# H_bridge.net
KiCad netlist of a schematic drawn in EAGLE
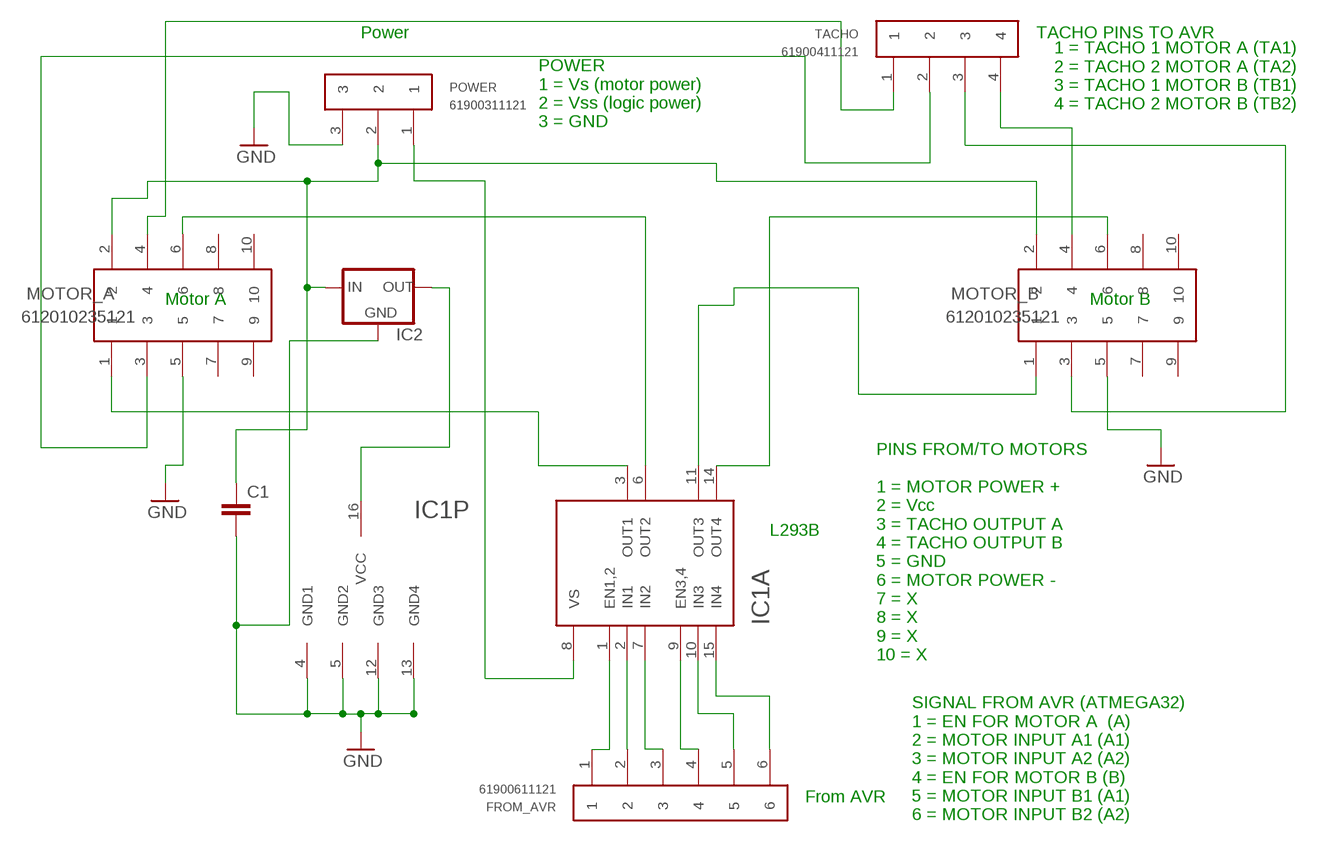
[diagram p0: schematic, sheet 1]

(export (version "E")
  (design (tool "Eeschema 10.0.6"))
  (components
    (comp (ref "C1")
      (value "C7.5/5")
      (footprint "eagle-import:C7.5B5")
      (libsource (lib "eagle-import") (part "C7.5/5"))
    )
    (comp (ref "FROM_AVR")
      (value "61900611121")
      (footprint "eagle-import:61900611121")
      (libsource (lib "eagle-import") (part "61900611121"))
    )
    (comp (ref "IC1")
      (value "L293D")
      (footprint "eagle-import:DIP16")
      (libsource (lib "eagle-import") (part "L293D"))
    )
    (comp (ref "IC2")
      (value "V_REG_78XX-TO-220")
      (footprint "eagle-import:TO-220-ALT")
      (libsource (lib "eagle-import") (part "V_REG_78XX-TO-220"))
    )
    (comp (ref "MOTOR_A")
      (value "612010235121")
      (footprint "eagle-import:612010235121")
      (libsource (lib "eagle-import") (part "612010235121"))
    )
    (comp (ref "MOTOR_B")
      (value "612010235121")
      (footprint "eagle-import:612010235121")
      (libsource (lib "eagle-import") (part "612010235121"))
    )
    (comp (ref "POWER")
      (value "61900311121")
      (footprint "eagle-import:61900311121")
      (libsource (lib "eagle-import") (part "61900311121"))
    )
    (comp (ref "TACHO")
      (value "61900411121")
      (footprint "eagle-import:61900411121")
      (libsource (lib "eagle-import") (part "61900411121"))
    )
  )
  (nets
    (net (code "1") (name "GND") (class "Default")
      (node (ref "C1") (pin "2") (pinfunction "2_2") (pintype "passive"))
      (node (ref "IC1") (pin "12") (pinfunction "GND3_12") (pintype "power_in"))
      (node (ref "IC1") (pin "13") (pinfunction "GND4_13") (pintype "power_in"))
      (node (ref "IC1") (pin "4") (pinfunction "GND1_4") (pintype "power_in"))
      (node (ref "IC1") (pin "5") (pinfunction "GND2_5") (pintype "power_in"))
      (node (ref "IC2") (pin "GND") (pinfunction "GND_GND") (pintype "input"))
      (node (ref "MOTOR_A") (pin "5") (pinfunction "5_5") (pintype "passive"))
      (node (ref "MOTOR_B") (pin "5") (pinfunction "5_5") (pintype "passive"))
      (node (ref "POWER") (pin "3") (pinfunction "3_3") (pintype "bidirectional"))
    )
    (net (code "2") (name "Net-(C1-Pad1)") (class "Default")
      (node (ref "C1") (pin "1") (pinfunction "1_1") (pintype "passive"))
      (node (ref "IC2") (pin "IN") (pinfunction "IN_IN") (pintype "input"))
      (node (ref "MOTOR_A") (pin "2") (pinfunction "2_2") (pintype "passive"))
      (node (ref "MOTOR_B") (pin "2") (pinfunction "2_2") (pintype "passive"))
      (node (ref "POWER") (pin "2") (pinfunction "2_2") (pintype "bidirectional"))
    )
    (net (code "3") (name "Net-(IC1A-EN1,2)") (class "Default")
      (node (ref "FROM_AVR") (pin "1") (pinfunction "1_1") (pintype "bidirectional"))
      (node (ref "IC1") (pin "1") (pinfunction "EN1,2_1") (pintype "input"))
    )
    (net (code "4") (name "Net-(IC1A-EN3,4)") (class "Default")
      (node (ref "FROM_AVR") (pin "4") (pinfunction "4_4") (pintype "bidirectional"))
      (node (ref "IC1") (pin "9") (pinfunction "EN3,4_9") (pintype "input"))
    )
    (net (code "5") (name "Net-(IC1A-IN1)") (class "Default")
      (node (ref "FROM_AVR") (pin "2") (pinfunction "2_2") (pintype "bidirectional"))
      (node (ref "IC1") (pin "2") (pinfunction "IN1_2") (pintype "input"))
    )
    (net (code "6") (name "Net-(IC1A-IN2)") (class "Default")
      (node (ref "FROM_AVR") (pin "3") (pinfunction "3_3") (pintype "bidirectional"))
      (node (ref "IC1") (pin "7") (pinfunction "IN2_7") (pintype "input"))
    )
    (net (code "7") (name "Net-(IC1A-IN3)") (class "Default")
      (node (ref "FROM_AVR") (pin "5") (pinfunction "5_5") (pintype "bidirectional"))
      (node (ref "IC1") (pin "10") (pinfunction "IN3_10") (pintype "input"))
    )
    (net (code "8") (name "Net-(IC1A-IN4)") (class "Default")
      (node (ref "FROM_AVR") (pin "6") (pinfunction "6_6") (pintype "bidirectional"))
      (node (ref "IC1") (pin "15") (pinfunction "IN4_15") (pintype "input"))
    )
    (net (code "9") (name "Net-(IC1A-OUT1)") (class "Default")
      (node (ref "IC1") (pin "3") (pinfunction "OUT1_3") (pintype "output"))
      (node (ref "MOTOR_A") (pin "1") (pinfunction "1_1") (pintype "passive"))
    )
    (net (code "10") (name "Net-(IC1A-OUT2)") (class "Default")
      (node (ref "IC1") (pin "6") (pinfunction "OUT2_6") (pintype "output"))
      (node (ref "MOTOR_A") (pin "6") (pinfunction "6_6") (pintype "passive"))
    )
    (net (code "11") (name "Net-(IC1A-OUT3)") (class "Default")
      (node (ref "IC1") (pin "11") (pinfunction "OUT3_11") (pintype "output"))
      (node (ref "MOTOR_B") (pin "1") (pinfunction "1_1") (pintype "passive"))
    )
    (net (code "12") (name "Net-(IC1A-OUT4)") (class "Default")
      (node (ref "IC1") (pin "14") (pinfunction "OUT4_14") (pintype "output"))
      (node (ref "MOTOR_B") (pin "6") (pinfunction "6_6") (pintype "passive"))
    )
    (net (code "13") (name "Net-(IC1A-VS)") (class "Default")
      (node (ref "IC1") (pin "8") (pinfunction "VS_8") (pintype "power_in"))
      (node (ref "POWER") (pin "1") (pinfunction "1_1") (pintype "bidirectional"))
    )
    (net (code "14") (name "Net-(IC1B-VCC)") (class "Default")
      (node (ref "IC1") (pin "16") (pinfunction "VCC_16") (pintype "power_in"))
      (node (ref "IC2") (pin "OUT") (pinfunction "OUT_OUT") (pintype "output"))
    )
    (net (code "15") (name "Net-(MOTOR_A-Pad3)") (class "Default")
      (node (ref "MOTOR_A") (pin "3") (pinfunction "3_3") (pintype "passive"))
      (node (ref "TACHO") (pin "2") (pinfunction "2_2") (pintype "bidirectional"))
    )
    (net (code "16") (name "Net-(MOTOR_A-Pad4)") (class "Default")
      (node (ref "MOTOR_A") (pin "4") (pinfunction "4_4") (pintype "passive"))
      (node (ref "TACHO") (pin "1") (pinfunction "1_1") (pintype "bidirectional"))
    )
    (net (code "17") (name "Net-(MOTOR_B-Pad3)") (class "Default")
      (node (ref "MOTOR_B") (pin "3") (pinfunction "3_3") (pintype "passive"))
      (node (ref "TACHO") (pin "3") (pinfunction "3_3") (pintype "bidirectional"))
    )
    (net (code "18") (name "Net-(MOTOR_B-Pad4)") (class "Default")
      (node (ref "MOTOR_B") (pin "4") (pinfunction "4_4") (pintype "passive"))
      (node (ref "TACHO") (pin "4") (pinfunction "4_4") (pintype "bidirectional"))
    )
    (net (code "19") (name "unconnected-(MOTOR_A-Pad7)") (class "Default")
      (node (ref "MOTOR_A") (pin "7") (pinfunction "7_7") (pintype "passive"))
    )
    (net (code "20") (name "unconnected-(MOTOR_A-Pad8)") (class "Default")
      (node (ref "MOTOR_A") (pin "8") (pinfunction "8_8") (pintype "passive"))
    )
    (net (code "21") (name "unconnected-(MOTOR_A-Pad9)") (class "Default")
      (node (ref "MOTOR_A") (pin "9") (pinfunction "9_9") (pintype "passive"))
    )
    (net (code "22") (name "unconnected-(MOTOR_A-Pad10)") (class "Default")
      (node (ref "MOTOR_A") (pin "10") (pinfunction "10_10") (pintype "passive"))
    )
    (net (code "23") (name "unconnected-(MOTOR_B-Pad7)") (class "Default")
      (node (ref "MOTOR_B") (pin "7") (pinfunction "7_7") (pintype "passive"))
    )
    (net (code "24") (name "unconnected-(MOTOR_B-Pad8)") (class "Default")
      (node (ref "MOTOR_B") (pin "8") (pinfunction "8_8") (pintype "passive"))
    )
    (net (code "25") (name "unconnected-(MOTOR_B-Pad9)") (class "Default")
      (node (ref "MOTOR_B") (pin "9") (pinfunction "9_9") (pintype "passive"))
    )
    (net (code "26") (name "unconnected-(MOTOR_B-Pad10)") (class "Default")
      (node (ref "MOTOR_B") (pin "10") (pinfunction "10_10") (pintype "passive"))
    )
  )
)
